# LSM303D.net
KiCad netlist of a schematic drawn in EAGLE
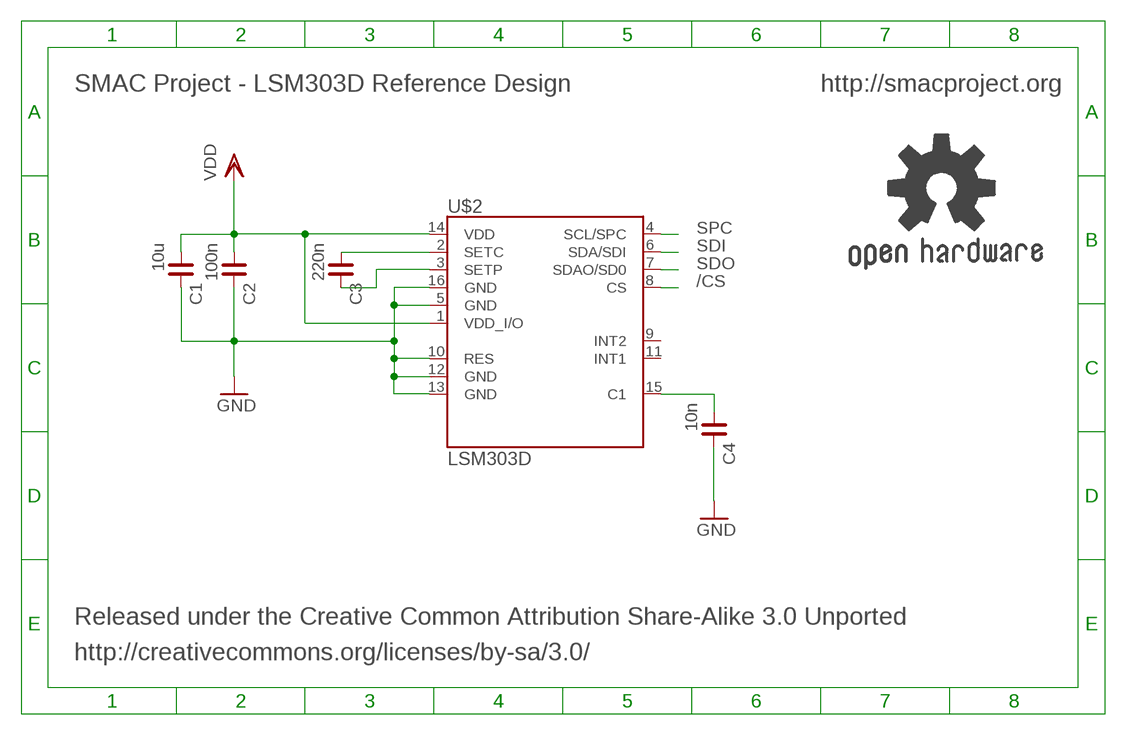
[diagram p0: schematic, sheet 1]

(export (version "E")
  (design (tool "Eeschema 10.0.6"))
  (components
    (comp (ref "C1")
      (value "10u")
      (footprint "eagle-import:C0402")
      (libsource (lib "eagle-import") (part "C_0402"))
    )
    (comp (ref "C2")
      (value "100n")
      (footprint "eagle-import:C0402")
      (libsource (lib "eagle-import") (part "C_0402"))
    )
    (comp (ref "C3")
      (value "220n")
      (footprint "eagle-import:C0402")
      (libsource (lib "eagle-import") (part "C_0402"))
    )
    (comp (ref "C4")
      (value "10n")
      (footprint "eagle-import:C0402")
      (libsource (lib "eagle-import") (part "C_0402"))
    )
    (comp (ref "GOLD_ORB_SM2")
      (value "OSHWLOGO_REF_SM")
      (footprint "eagle-import:OSHW2REF")
      (libsource (lib "eagle-import") (part "OSHWLOGO_REF_SM"))
    )
    (comp (ref "U$2")
      (value "LSM303D")
      (footprint "eagle-import:LGA16-3MM")
      (libsource (lib "eagle-import") (part "LSM303D"))
    )
  )
  (nets
    (net (code "1") (name "/SDI") (class "Default")
      (node (ref "U$2") (pin "6") (pinfunction "SDA/SDI_6") (pintype "bidirectional"))
    )
    (net (code "2") (name "/SDO") (class "Default")
      (node (ref "U$2") (pin "7") (pinfunction "SDAO/SD0_7") (pintype "bidirectional"))
    )
    (net (code "3") (name "/SPC") (class "Default")
      (node (ref "U$2") (pin "4") (pinfunction "SCL/SPC_4") (pintype "bidirectional"))
    )
    (net (code "4") (name "/{slash}CS") (class "Default")
      (node (ref "U$2") (pin "8") (pinfunction "CS_8") (pintype "bidirectional"))
    )
    (net (code "5") (name "GND") (class "Default")
      (node (ref "C1") (pin "2") (pinfunction "2_2") (pintype "passive"))
      (node (ref "C2") (pin "2") (pinfunction "2_2") (pintype "passive"))
      (node (ref "C4") (pin "2") (pinfunction "2_2") (pintype "passive"))
      (node (ref "U$2") (pin "10") (pinfunction "RES_10") (pintype "bidirectional"))
      (node (ref "U$2") (pin "12") (pinfunction "GND_12") (pintype "bidirectional"))
      (node (ref "U$2") (pin "13") (pinfunction "GND_13") (pintype "bidirectional"))
      (node (ref "U$2") (pin "16") (pinfunction "GND_16") (pintype "bidirectional"))
      (node (ref "U$2") (pin "5") (pinfunction "GND_5") (pintype "bidirectional"))
    )
    (net (code "6") (name "Net-(U$2-C1)") (class "Default")
      (node (ref "C4") (pin "1") (pinfunction "1_1") (pintype "passive"))
      (node (ref "U$2") (pin "15") (pinfunction "C1_15") (pintype "bidirectional"))
    )
    (net (code "7") (name "Net-(U$2-SETC)") (class "Default")
      (node (ref "C3") (pin "1") (pinfunction "1_1") (pintype "passive"))
      (node (ref "U$2") (pin "2") (pinfunction "SETC_2") (pintype "bidirectional"))
    )
    (net (code "8") (name "Net-(U$2-SETP)") (class "Default")
      (node (ref "C3") (pin "2") (pinfunction "2_2") (pintype "passive"))
      (node (ref "U$2") (pin "3") (pinfunction "SETP_3") (pintype "bidirectional"))
    )
    (net (code "9") (name "VDD") (class "Default")
      (node (ref "C1") (pin "1") (pinfunction "1_1") (pintype "passive"))
      (node (ref "C2") (pin "1") (pinfunction "1_1") (pintype "passive"))
      (node (ref "U$2") (pin "1") (pinfunction "VDD_I/O_1") (pintype "bidirectional"))
      (node (ref "U$2") (pin "14") (pinfunction "VDD_14") (pintype "bidirectional"))
    )
    (net (code "10") (name "unconnected-(U$2-INT1-Pad11)") (class "Default")
      (node (ref "U$2") (pin "11") (pinfunction "INT1_11") (pintype "bidirectional"))
    )
    (net (code "11") (name "unconnected-(U$2-INT2-Pad9)") (class "Default")
      (node (ref "U$2") (pin "9") (pinfunction "INT2_9") (pintype "bidirectional"))
    )
  )
)
